# position_sensors.net
KiCad netlist of a schematic drawn in Altium Designer
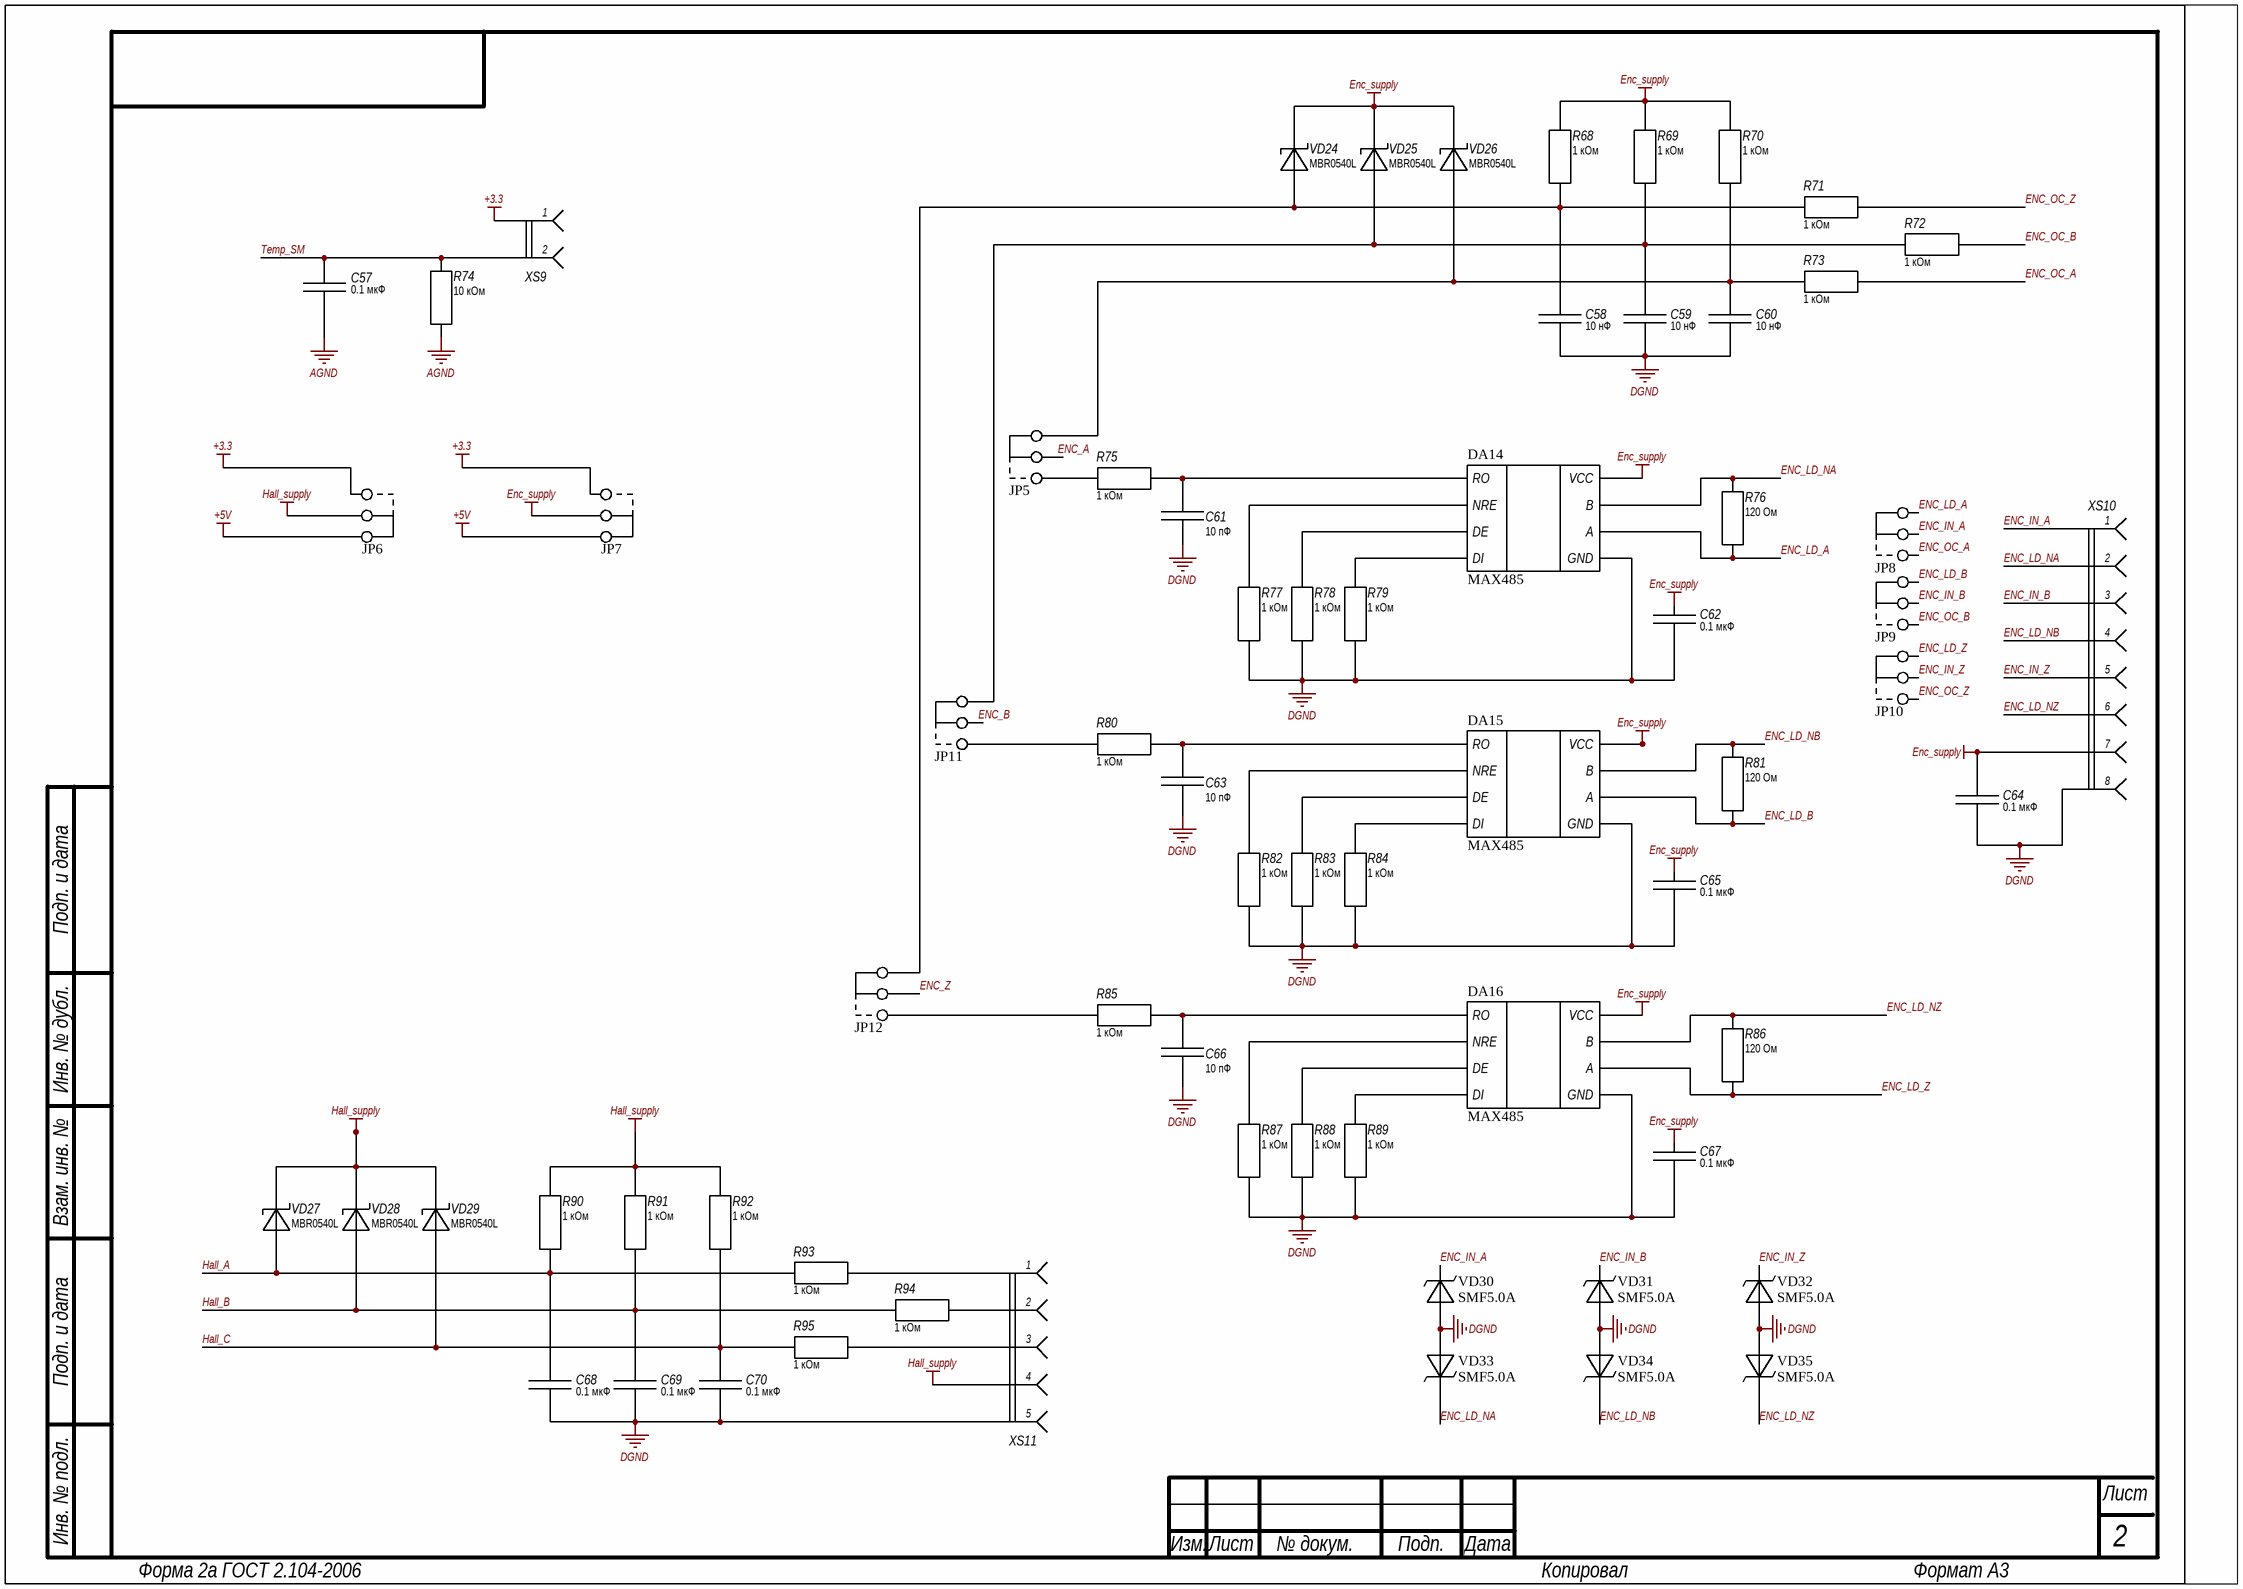
[diagram p0: position_sensors.SchDoc]

(export (version "E")
  (design (tool "Eeschema 10.0.6"))
  (components
    (comp (ref "C57")
      (value "0.1 мкФ")
      (footprint "CC0805")
      (fields (field (name "VOLTAGE") "50 В") (field (name "Comment") "Capacitor"))
      (libsource (lib "Main_components") (part "Capacitor"))
    )
    (comp (ref "C58")
      (value "10 нФ")
      (footprint "CC0805")
      (fields (field (name "VOLTAGE") "16В") (field (name "Comment") "Capacitor"))
      (libsource (lib "Main_components") (part "Capacitor"))
    )
    (comp (ref "C59")
      (value "10 нФ")
      (footprint "CC0805")
      (fields (field (name "VOLTAGE") "16В") (field (name "Comment") "Capacitor"))
      (libsource (lib "Main_components") (part "Capacitor"))
    )
    (comp (ref "C60")
      (value "10 нФ")
      (footprint "CC0603")
      (fields (field (name "VOLTAGE") "50В") (field (name "Comment") "Capacitor"))
      (libsource (lib "Main_components") (part "Capacitor"))
    )
    (comp (ref "C61")
      (value "10 пФ")
      (footprint "CC0603")
      (fields (field (name "VOLTAGE") "50В") (field (name "Comment") "Capacitor"))
      (libsource (lib "Main_components") (part "Capacitor"))
    )
    (comp (ref "C62")
      (value "0.1 мкФ")
      (footprint "CC0603")
      (fields (field (name "VOLTAGE") "16В") (field (name "Comment") "Capacitor"))
      (libsource (lib "Main_components") (part "Capacitor"))
    )
    (comp (ref "C63")
      (value "10 пФ")
      (footprint "CC0603")
      (fields (field (name "VOLTAGE") "50В") (field (name "Comment") "Capacitor"))
      (libsource (lib "Main_components") (part "Capacitor"))
    )
    (comp (ref "C64")
      (value "0.1 мкФ")
      (footprint "CC0603")
      (fields (field (name "VOLTAGE") "16В") (field (name "Comment") "Capacitor"))
      (libsource (lib "Main_components") (part "Capacitor"))
    )
    (comp (ref "C65")
      (value "0.1 мкФ")
      (footprint "CC0603")
      (fields (field (name "VOLTAGE") "16В") (field (name "Comment") "Capacitor"))
      (libsource (lib "Main_components") (part "Capacitor"))
    )
    (comp (ref "C66")
      (value "10 пФ")
      (footprint "CC0603")
      (fields (field (name "VOLTAGE") "50В") (field (name "Comment") "Capacitor"))
      (libsource (lib "Main_components") (part "Capacitor"))
    )
    (comp (ref "C67")
      (value "0.1 мкФ")
      (footprint "CC0603")
      (fields (field (name "VOLTAGE") "16В") (field (name "Comment") "Capacitor"))
      (libsource (lib "Main_components") (part "Capacitor"))
    )
    (comp (ref "C68")
      (value "0.1 мкФ")
      (footprint "CC0805")
      (fields (field (name "VOLTAGE") "50В") (field (name "Comment") "Capacitor"))
      (libsource (lib "Main_components") (part "Capacitor"))
    )
    (comp (ref "C69")
      (value "0.1 мкФ")
      (footprint "CC0805")
      (fields (field (name "VOLTAGE") "50В") (field (name "Comment") "Capacitor"))
      (libsource (lib "Main_components") (part "Capacitor"))
    )
    (comp (ref "C70")
      (value "0.1 мкФ")
      (footprint "CC0805")
      (fields (field (name "VOLTAGE") "50В") (field (name "Comment") "Capacitor"))
      (libsource (lib "Main_components") (part "Capacitor"))
    )
    (comp (ref "DA14")
      (value "MAX485")
      (footprint "SO8")
      (libsource (lib "Microcircuits") (part "MAX485ESA"))
    )
    (comp (ref "DA15")
      (value "MAX485")
      (footprint "SO8")
      (libsource (lib "Microcircuits") (part "MAX485ESA"))
    )
    (comp (ref "DA16")
      (value "MAX485")
      (footprint "SO8")
      (libsource (lib "Microcircuits") (part "MAX485ESA"))
    )
    (comp (ref "JP5") (value "Jumper") (footprint "PLS3") (libsource (lib "Connectors") (part "Jumper")))
    (comp (ref "JP6") (value "Jumper") (footprint "PLS3") (libsource (lib "Connectors") (part "Jumper")))
    (comp (ref "JP7") (value "Jumper") (footprint "PLS3") (libsource (lib "Connectors") (part "Jumper")))
    (comp (ref "JP8") (value "Jumper") (footprint "PLS3") (libsource (lib "Connectors") (part "Jumper")))
    (comp (ref "JP9") (value "Jumper") (footprint "PLS3") (libsource (lib "Connectors") (part "Jumper")))
    (comp (ref "JP10") (value "Jumper") (footprint "PLS3") (libsource (lib "Connectors") (part "Jumper")))
    (comp (ref "JP11") (value "Jumper") (footprint "PLS3") (libsource (lib "Connectors") (part "Jumper")))
    (comp (ref "JP12") (value "Jumper") (footprint "PLS3") (libsource (lib "Connectors") (part "Jumper")))
    (comp (ref "R68")
      (value "1 кОм")
      (footprint "RC1206")
      (fields (field (name "POWER") "250 мВт") (field (name "Comment") "Resistor"))
      (libsource (lib "Main_components") (part "Resistor"))
    )
    (comp (ref "R69")
      (value "1 кОм")
      (footprint "RC1206")
      (fields (field (name "POWER") "250 мВт") (field (name "Comment") "Resistor"))
      (libsource (lib "Main_components") (part "Resistor"))
    )
    (comp (ref "R70")
      (value "1 кОм")
      (footprint "RC1206")
      (fields (field (name "POWER") "250 мВт") (field (name "Comment") "Resistor"))
      (libsource (lib "Main_components") (part "Resistor"))
    )
    (comp (ref "R71")
      (value "1 кОм")
      (footprint "RC1206")
      (fields (field (name "POWER") "250 мВт") (field (name "Comment") "Resistor"))
      (libsource (lib "Main_components") (part "Resistor"))
    )
    (comp (ref "R72")
      (value "1 кОм")
      (footprint "RC1206")
      (fields (field (name "POWER") "250 мВт") (field (name "Comment") "Resistor"))
      (libsource (lib "Main_components") (part "Resistor"))
    )
    (comp (ref "R73")
      (value "1 кОм")
      (footprint "RC1206")
      (fields (field (name "POWER") "250 мВт") (field (name "Comment") "Resistor"))
      (libsource (lib "Main_components") (part "Resistor"))
    )
    (comp (ref "R74")
      (value "10 кОм")
      (footprint "RC0805")
      (fields (field (name "POWER") "125 мВт") (field (name "Comment") "Resistor"))
      (libsource (lib "Main_components") (part "Resistor"))
    )
    (comp (ref "R75")
      (value "1 кОм")
      (footprint "RC0603")
      (fields (field (name "POWER") "100мВт") (field (name "Comment") "Resistor"))
      (libsource (lib "Main_components") (part "Resistor"))
    )
    (comp (ref "R76")
      (value "120 Ом")
      (footprint "RC1206")
      (fields (field (name "POWER") "250 мВт") (field (name "Comment") "Resistor"))
      (libsource (lib "Main_components") (part "Resistor"))
    )
    (comp (ref "R77")
      (value "1 кОм")
      (footprint "RC0603")
      (fields (field (name "POWER") "100 мВт") (field (name "Comment") "Resistor"))
      (libsource (lib "Main_components") (part "Resistor"))
    )
    (comp (ref "R78")
      (value "1 кОм")
      (footprint "RC0603")
      (fields (field (name "POWER") "100 мВт") (field (name "Comment") "Resistor"))
      (libsource (lib "Main_components") (part "Resistor"))
    )
    (comp (ref "R79")
      (value "1 кОм")
      (footprint "RC0603")
      (fields (field (name "POWER") "100 мВт") (field (name "Comment") "Resistor"))
      (libsource (lib "Main_components") (part "Resistor"))
    )
    (comp (ref "R80")
      (value "1 кОм")
      (footprint "RC0603")
      (fields (field (name "POWER") "100мВт") (field (name "Comment") "Resistor"))
      (libsource (lib "Main_components") (part "Resistor"))
    )
    (comp (ref "R81")
      (value "120 Ом")
      (footprint "RC1206")
      (fields (field (name "POWER") "250 мВт") (field (name "Comment") "Resistor"))
      (libsource (lib "Main_components") (part "Resistor"))
    )
    (comp (ref "R82")
      (value "1 кОм")
      (footprint "RC0603")
      (fields (field (name "POWER") "100 мВт") (field (name "Comment") "Resistor"))
      (libsource (lib "Main_components") (part "Resistor"))
    )
    (comp (ref "R83")
      (value "1 кОм")
      (footprint "RC0603")
      (fields (field (name "POWER") "100 мВт") (field (name "Comment") "Resistor"))
      (libsource (lib "Main_components") (part "Resistor"))
    )
    (comp (ref "R84")
      (value "1 кОм")
      (footprint "RC0603")
      (fields (field (name "POWER") "100 мВт") (field (name "Comment") "Resistor"))
      (libsource (lib "Main_components") (part "Resistor"))
    )
    (comp (ref "R85")
      (value "1 кОм")
      (footprint "RC0603")
      (fields (field (name "POWER") "100мВт") (field (name "Comment") "Resistor"))
      (libsource (lib "Main_components") (part "Resistor"))
    )
    (comp (ref "R86")
      (value "120 Ом")
      (footprint "RC1206")
      (fields (field (name "POWER") "250 мВт") (field (name "Comment") "Resistor"))
      (libsource (lib "Main_components") (part "Resistor"))
    )
    (comp (ref "R87")
      (value "1 кОм")
      (footprint "RC0603")
      (fields (field (name "POWER") "100 мВт") (field (name "Comment") "Resistor"))
      (libsource (lib "Main_components") (part "Resistor"))
    )
    (comp (ref "R88")
      (value "1 кОм")
      (footprint "RC0603")
      (fields (field (name "POWER") "100 мВт") (field (name "Comment") "Resistor"))
      (libsource (lib "Main_components") (part "Resistor"))
    )
    (comp (ref "R89")
      (value "1 кОм")
      (footprint "RC0603")
      (fields (field (name "POWER") "100 мВт") (field (name "Comment") "Resistor"))
      (libsource (lib "Main_components") (part "Resistor"))
    )
    (comp (ref "R90")
      (value "1 кОм")
      (footprint "RC1206")
      (fields (field (name "POWER") "250 мВт") (field (name "Comment") "Resistor"))
      (libsource (lib "Main_components") (part "Resistor"))
    )
    (comp (ref "R91")
      (value "1 кОм")
      (footprint "RC1206")
      (fields (field (name "POWER") "250 мВт") (field (name "Comment") "Resistor"))
      (libsource (lib "Main_components") (part "Resistor"))
    )
    (comp (ref "R92")
      (value "1 кОм")
      (footprint "RC1206")
      (fields (field (name "POWER") "250 мВт") (field (name "Comment") "Resistor"))
      (libsource (lib "Main_components") (part "Resistor"))
    )
    (comp (ref "R93")
      (value "1 кОм")
      (footprint "RC1206")
      (fields (field (name "POWER") "250 мВт") (field (name "Comment") "Resistor"))
      (libsource (lib "Main_components") (part "Resistor"))
    )
    (comp (ref "R94")
      (value "1 кОм")
      (footprint "RC1206")
      (fields (field (name "POWER") "250 мВт") (field (name "Comment") "Resistor"))
      (libsource (lib "Main_components") (part "Resistor"))
    )
    (comp (ref "R95")
      (value "1 кОм")
      (footprint "RC1206")
      (fields (field (name "POWER") "250 мВт") (field (name "Comment") "Resistor"))
      (libsource (lib "Main_components") (part "Resistor"))
    )
    (comp (ref "VD24")
      (value "MBR0540L")
      (footprint "SOD123")
      (libsource (lib "Main_components") (part "Shotki"))
    )
    (comp (ref "VD25")
      (value "MBR0540L")
      (footprint "SOD123")
      (libsource (lib "Main_components") (part "Shotki"))
    )
    (comp (ref "VD26")
      (value "MBR0540L")
      (footprint "SOD123")
      (libsource (lib "Main_components") (part "Shotki"))
    )
    (comp (ref "VD27")
      (value "MBR0540L")
      (footprint "SOD123")
      (libsource (lib "Main_components") (part "Shotki"))
    )
    (comp (ref "VD28")
      (value "MBR0540L")
      (footprint "SOD123")
      (libsource (lib "Main_components") (part "Shotki"))
    )
    (comp (ref "VD29")
      (value "MBR0540L")
      (footprint "SOD123")
      (libsource (lib "Main_components") (part "Shotki"))
    )
    (comp (ref "VD30")
      (value "SMF5.0A")
      (footprint "D0-124AC")
      (libsource (lib "Main_components") (part "TVS Diode"))
    )
    (comp (ref "VD31")
      (value "SMF5.0A")
      (footprint "D0-124AC")
      (libsource (lib "Main_components") (part "TVS Diode"))
    )
    (comp (ref "VD32")
      (value "SMF5.0A")
      (footprint "D0-124AC")
      (libsource (lib "Main_components") (part "TVS Diode"))
    )
    (comp (ref "VD33")
      (value "SMF5.0A")
      (footprint "D0-124AC")
      (libsource (lib "Main_components") (part "TVS Diode"))
    )
    (comp (ref "VD34")
      (value "SMF5.0A")
      (footprint "D0-124AC")
      (libsource (lib "Main_components") (part "TVS Diode"))
    )
    (comp (ref "VD35")
      (value "SMF5.0A")
      (footprint "D0-124AC")
      (libsource (lib "Main_components") (part "TVS Diode"))
    )
    (comp (ref "XS9")
      (value "JST-Male-2")
      (footprint "JST-2")
      (libsource (lib "Connectors") (part "JST-Male-2"))
    )
    (comp (ref "XS10")
      (value "DG141V-2.54-05P-14-00AH")
      (footprint "DG141V-2.54-08P")
      (libsource (lib "Connectors") (part "DG141V-2.54-08P-14-00A(H)"))
    )
    (comp (ref "XS11")
      (value "DG141V-2.54-05P-14-00AH")
      (footprint "DG141V-2.54-05P")
      (libsource (lib "Connectors") (part "DG141V-2.54-05P-14-00AH"))
    )
  )
  (nets
    (net (code "1") (name "+3.3") (class "Default")
      (node (ref "JP6") (pin "1") (pinfunction "4_1") (pintype "passive"))
      (node (ref "JP7") (pin "1") (pinfunction "4_1") (pintype "passive"))
      (node (ref "XS9") (pin "1") (pinfunction "1_1") (pintype "passive"))
    )
    (net (code "2") (name "+5V") (class "Default")
      (node (ref "JP6") (pin "3") (pinfunction "6_3") (pintype "passive"))
      (node (ref "JP7") (pin "3") (pinfunction "6_3") (pintype "passive"))
    )
    (net (code "3") (name "/ENC_A") (class "Default")
      (node (ref "JP5") (pin "2") (pinfunction "5_2") (pintype "passive"))
    )
    (net (code "4") (name "/ENC_B") (class "Default")
      (node (ref "JP11") (pin "2") (pinfunction "5_2") (pintype "passive"))
    )
    (net (code "5") (name "/ENC_IN_A") (class "Default")
      (node (ref "JP8") (pin "2") (pinfunction "5_2") (pintype "passive"))
      (node (ref "VD30") (pin "C") (pinfunction "C_C") (pintype "passive"))
      (node (ref "XS10") (pin "1") (pinfunction "1_1") (pintype "passive"))
    )
    (net (code "6") (name "/ENC_IN_B") (class "Default")
      (node (ref "JP9") (pin "2") (pinfunction "5_2") (pintype "passive"))
      (node (ref "VD31") (pin "C") (pinfunction "C_C") (pintype "passive"))
      (node (ref "XS10") (pin "3") (pinfunction "3_3") (pintype "passive"))
    )
    (net (code "7") (name "/ENC_IN_Z") (class "Default")
      (node (ref "JP10") (pin "2") (pinfunction "5_2") (pintype "passive"))
      (node (ref "VD32") (pin "C") (pinfunction "C_C") (pintype "passive"))
      (node (ref "XS10") (pin "5") (pinfunction "5_5") (pintype "passive"))
    )
    (net (code "8") (name "/ENC_LD_A") (class "Default")
      (node (ref "DA14") (pin "7") (pinfunction "A_7") (pintype "passive"))
      (node (ref "JP8") (pin "3") (pinfunction "6_3") (pintype "passive"))
      (node (ref "R76") (pin "1") (pinfunction "1_1") (pintype "passive"))
    )
    (net (code "9") (name "/ENC_LD_B") (class "Default")
      (node (ref "DA15") (pin "7") (pinfunction "A_7") (pintype "passive"))
      (node (ref "JP9") (pin "3") (pinfunction "6_3") (pintype "passive"))
      (node (ref "R81") (pin "1") (pinfunction "1_1") (pintype "passive"))
    )
    (net (code "10") (name "/ENC_LD_NA") (class "Default")
      (node (ref "DA14") (pin "6") (pinfunction "B_6") (pintype "passive"))
      (node (ref "R76") (pin "2") (pinfunction "2_2") (pintype "passive"))
      (node (ref "VD33") (pin "C") (pinfunction "C_C") (pintype "passive"))
      (node (ref "XS10") (pin "2") (pinfunction "2_2") (pintype "passive"))
    )
    (net (code "11") (name "/ENC_LD_NB") (class "Default")
      (node (ref "DA15") (pin "6") (pinfunction "B_6") (pintype "passive"))
      (node (ref "R81") (pin "2") (pinfunction "2_2") (pintype "passive"))
      (node (ref "VD34") (pin "C") (pinfunction "C_C") (pintype "passive"))
      (node (ref "XS10") (pin "4") (pinfunction "4_4") (pintype "passive"))
    )
    (net (code "12") (name "/ENC_LD_NZ") (class "Default")
      (node (ref "DA16") (pin "6") (pinfunction "B_6") (pintype "passive"))
      (node (ref "R86") (pin "2") (pinfunction "2_2") (pintype "passive"))
      (node (ref "VD35") (pin "C") (pinfunction "C_C") (pintype "passive"))
      (node (ref "XS10") (pin "6") (pinfunction "6_6") (pintype "passive"))
    )
    (net (code "13") (name "/ENC_LD_Z") (class "Default")
      (node (ref "DA16") (pin "7") (pinfunction "A_7") (pintype "passive"))
      (node (ref "JP10") (pin "3") (pinfunction "6_3") (pintype "passive"))
      (node (ref "R86") (pin "1") (pinfunction "1_1") (pintype "passive"))
    )
    (net (code "14") (name "/ENC_OC_A") (class "Default")
      (node (ref "JP8") (pin "1") (pinfunction "4_1") (pintype "passive"))
      (node (ref "R73") (pin "2") (pinfunction "2_2") (pintype "passive"))
    )
    (net (code "15") (name "/ENC_OC_B") (class "Default")
      (node (ref "JP9") (pin "1") (pinfunction "4_1") (pintype "passive"))
      (node (ref "R72") (pin "2") (pinfunction "2_2") (pintype "passive"))
    )
    (net (code "16") (name "/ENC_OC_Z") (class "Default")
      (node (ref "JP10") (pin "1") (pinfunction "4_1") (pintype "passive"))
      (node (ref "R71") (pin "2") (pinfunction "2_2") (pintype "passive"))
    )
    (net (code "17") (name "/ENC_Z") (class "Default")
      (node (ref "JP12") (pin "2") (pinfunction "5_2") (pintype "passive"))
    )
    (net (code "18") (name "/Hall_A") (class "Default")
      (node (ref "C68") (pin "2") (pinfunction "2_2") (pintype "passive"))
      (node (ref "R90") (pin "1") (pinfunction "1_1") (pintype "passive"))
      (node (ref "R93") (pin "1") (pinfunction "1_1") (pintype "passive"))
      (node (ref "VD27") (pin "A") (pinfunction "A_A") (pintype "passive"))
    )
    (net (code "19") (name "/Hall_B") (class "Default")
      (node (ref "C69") (pin "2") (pinfunction "2_2") (pintype "passive"))
      (node (ref "R91") (pin "1") (pinfunction "1_1") (pintype "passive"))
      (node (ref "R94") (pin "1") (pinfunction "1_1") (pintype "passive"))
      (node (ref "VD28") (pin "A") (pinfunction "A_A") (pintype "passive"))
    )
    (net (code "20") (name "/Hall_C") (class "Default")
      (node (ref "C70") (pin "2") (pinfunction "2_2") (pintype "passive"))
      (node (ref "R92") (pin "1") (pinfunction "1_1") (pintype "passive"))
      (node (ref "R95") (pin "1") (pinfunction "1_1") (pintype "passive"))
      (node (ref "VD29") (pin "A") (pinfunction "A_A") (pintype "passive"))
    )
    (net (code "21") (name "/Temp_SM") (class "Default")
      (node (ref "C57") (pin "2") (pinfunction "2_2") (pintype "passive"))
      (node (ref "R74") (pin "1") (pinfunction "1_1") (pintype "passive"))
      (node (ref "XS9") (pin "2") (pinfunction "2_2") (pintype "passive"))
    )
    (net (code "22") (name "AGND") (class "Default")
      (node (ref "C57") (pin "1") (pinfunction "1_1") (pintype "passive"))
      (node (ref "R74") (pin "2") (pinfunction "2_2") (pintype "passive"))
    )
    (net (code "23") (name "DGND") (class "Default")
      (node (ref "C58") (pin "1") (pinfunction "1_1") (pintype "passive"))
      (node (ref "C59") (pin "1") (pinfunction "1_1") (pintype "passive"))
      (node (ref "C60") (pin "1") (pinfunction "1_1") (pintype "passive"))
      (node (ref "C61") (pin "2") (pinfunction "2_2") (pintype "passive"))
      (node (ref "C62") (pin "1") (pinfunction "1_1") (pintype "passive"))
      (node (ref "C63") (pin "2") (pinfunction "2_2") (pintype "passive"))
      (node (ref "C64") (pin "1") (pinfunction "1_1") (pintype "passive"))
      (node (ref "C65") (pin "1") (pinfunction "1_1") (pintype "passive"))
      (node (ref "C66") (pin "2") (pinfunction "2_2") (pintype "passive"))
      (node (ref "C67") (pin "1") (pinfunction "1_1") (pintype "passive"))
      (node (ref "C68") (pin "1") (pinfunction "1_1") (pintype "passive"))
      (node (ref "C69") (pin "1") (pinfunction "1_1") (pintype "passive"))
      (node (ref "C70") (pin "1") (pinfunction "1_1") (pintype "passive"))
      (node (ref "DA14") (pin "8") (pinfunction "GND_8") (pintype "passive"))
      (node (ref "DA15") (pin "8") (pinfunction "GND_8") (pintype "passive"))
      (node (ref "DA16") (pin "8") (pinfunction "GND_8") (pintype "passive"))
      (node (ref "R77") (pin "2") (pinfunction "2_2") (pintype "passive"))
      (node (ref "R78") (pin "2") (pinfunction "2_2") (pintype "passive"))
      (node (ref "R79") (pin "2") (pinfunction "2_2") (pintype "passive"))
      (node (ref "R82") (pin "2") (pinfunction "2_2") (pintype "passive"))
      (node (ref "R83") (pin "2") (pinfunction "2_2") (pintype "passive"))
      (node (ref "R84") (pin "2") (pinfunction "2_2") (pintype "passive"))
      (node (ref "R87") (pin "2") (pinfunction "2_2") (pintype "passive"))
      (node (ref "R88") (pin "2") (pinfunction "2_2") (pintype "passive"))
      (node (ref "R89") (pin "2") (pinfunction "2_2") (pintype "passive"))
      (node (ref "VD30") (pin "A") (pinfunction "A_A") (pintype "passive"))
      (node (ref "VD31") (pin "A") (pinfunction "A_A") (pintype "passive"))
      (node (ref "VD32") (pin "A") (pinfunction "A_A") (pintype "passive"))
      (node (ref "VD33") (pin "A") (pinfunction "A_A") (pintype "passive"))
      (node (ref "VD34") (pin "A") (pinfunction "A_A") (pintype "passive"))
      (node (ref "VD35") (pin "A") (pinfunction "A_A") (pintype "passive"))
      (node (ref "XS10") (pin "8") (pinfunction "8_8") (pintype "passive"))
      (node (ref "XS11") (pin "5") (pinfunction "5_5") (pintype "passive"))
    )
    (net (code "24") (name "Enc_supply") (class "Default")
      (node (ref "C62") (pin "2") (pinfunction "2_2") (pintype "passive"))
      (node (ref "C64") (pin "2") (pinfunction "2_2") (pintype "passive"))
      (node (ref "C65") (pin "2") (pinfunction "2_2") (pintype "passive"))
      (node (ref "C67") (pin "2") (pinfunction "2_2") (pintype "passive"))
      (node (ref "DA14") (pin "5") (pinfunction "VCC_5") (pintype "passive"))
      (node (ref "DA15") (pin "5") (pinfunction "VCC_5") (pintype "passive"))
      (node (ref "DA16") (pin "5") (pinfunction "VCC_5") (pintype "passive"))
      (node (ref "JP7") (pin "2") (pinfunction "5_2") (pintype "passive"))
      (node (ref "R68") (pin "2") (pinfunction "2_2") (pintype "passive"))
      (node (ref "R69") (pin "2") (pinfunction "2_2") (pintype "passive"))
      (node (ref "R70") (pin "2") (pinfunction "2_2") (pintype "passive"))
      (node (ref "VD24") (pin "C") (pinfunction "C_C") (pintype "passive"))
      (node (ref "VD25") (pin "C") (pinfunction "C_C") (pintype "passive"))
      (node (ref "VD26") (pin "C") (pinfunction "C_C") (pintype "passive"))
      (node (ref "XS10") (pin "7") (pinfunction "7_7") (pintype "passive"))
    )
    (net (code "25") (name "Hall_supply") (class "Default")
      (node (ref "JP6") (pin "2") (pinfunction "5_2") (pintype "passive"))
      (node (ref "R90") (pin "2") (pinfunction "2_2") (pintype "passive"))
      (node (ref "R91") (pin "2") (pinfunction "2_2") (pintype "passive"))
      (node (ref "R92") (pin "2") (pinfunction "2_2") (pintype "passive"))
      (node (ref "VD27") (pin "C") (pinfunction "C_C") (pintype "passive"))
      (node (ref "VD28") (pin "C") (pinfunction "C_C") (pintype "passive"))
      (node (ref "VD29") (pin "C") (pinfunction "C_C") (pintype "passive"))
      (node (ref "XS11") (pin "4") (pinfunction "4_4") (pintype "passive"))
    )
    (net (code "26") (name "Net-(DA14-DE)") (class "Default")
      (node (ref "DA14") (pin "3") (pinfunction "DE_3") (pintype "passive"))
      (node (ref "R78") (pin "1") (pinfunction "1_1") (pintype "passive"))
    )
    (net (code "27") (name "Net-(DA14-DI)") (class "Default")
      (node (ref "DA14") (pin "4") (pinfunction "DI_4") (pintype "passive"))
      (node (ref "R79") (pin "1") (pinfunction "1_1") (pintype "passive"))
    )
    (net (code "28") (name "Net-(DA14-NRE)") (class "Default")
      (node (ref "DA14") (pin "2") (pinfunction "NRE_2") (pintype "passive"))
      (node (ref "R77") (pin "1") (pinfunction "1_1") (pintype "passive"))
    )
    (net (code "29") (name "Net-(DA14-RO)") (class "Default")
      (node (ref "C61") (pin "1") (pinfunction "1_1") (pintype "passive"))
      (node (ref "DA14") (pin "1") (pinfunction "RO_1") (pintype "passive"))
      (node (ref "R75") (pin "1") (pinfunction "1_1") (pintype "passive"))
    )
    (net (code "30") (name "Net-(DA15-DE)") (class "Default")
      (node (ref "DA15") (pin "3") (pinfunction "DE_3") (pintype "passive"))
      (node (ref "R83") (pin "1") (pinfunction "1_1") (pintype "passive"))
    )
    (net (code "31") (name "Net-(DA15-DI)") (class "Default")
      (node (ref "DA15") (pin "4") (pinfunction "DI_4") (pintype "passive"))
      (node (ref "R84") (pin "1") (pinfunction "1_1") (pintype "passive"))
    )
    (net (code "32") (name "Net-(DA15-NRE)") (class "Default")
      (node (ref "DA15") (pin "2") (pinfunction "NRE_2") (pintype "passive"))
      (node (ref "R82") (pin "1") (pinfunction "1_1") (pintype "passive"))
    )
    (net (code "33") (name "Net-(DA15-RO)") (class "Default")
      (node (ref "C63") (pin "1") (pinfunction "1_1") (pintype "passive"))
      (node (ref "DA15") (pin "1") (pinfunction "RO_1") (pintype "passive"))
      (node (ref "R80") (pin "1") (pinfunction "1_1") (pintype "passive"))
    )
    (net (code "34") (name "Net-(DA16-DE)") (class "Default")
      (node (ref "DA16") (pin "3") (pinfunction "DE_3") (pintype "passive"))
      (node (ref "R88") (pin "1") (pinfunction "1_1") (pintype "passive"))
    )
    (net (code "35") (name "Net-(DA16-DI)") (class "Default")
      (node (ref "DA16") (pin "4") (pinfunction "DI_4") (pintype "passive"))
      (node (ref "R89") (pin "1") (pinfunction "1_1") (pintype "passive"))
    )
    (net (code "36") (name "Net-(DA16-NRE)") (class "Default")
      (node (ref "DA16") (pin "2") (pinfunction "NRE_2") (pintype "passive"))
      (node (ref "R87") (pin "1") (pinfunction "1_1") (pintype "passive"))
    )
    (net (code "37") (name "Net-(DA16-RO)") (class "Default")
      (node (ref "C66") (pin "1") (pinfunction "1_1") (pintype "passive"))
      (node (ref "DA16") (pin "1") (pinfunction "RO_1") (pintype "passive"))
      (node (ref "R85") (pin "1") (pinfunction "1_1") (pintype "passive"))
    )
    (net (code "38") (name "Net-(JP5-4)") (class "Default")
      (node (ref "JP5") (pin "1") (pinfunction "4_1") (pintype "passive"))
      (node (ref "R75") (pin "2") (pinfunction "2_2") (pintype "passive"))
    )
    (net (code "39") (name "Net-(JP5-6)") (class "Default")
      (node (ref "C60") (pin "2") (pinfunction "2_2") (pintype "passive"))
      (node (ref "JP5") (pin "3") (pinfunction "6_3") (pintype "passive"))
      (node (ref "R70") (pin "1") (pinfunction "1_1") (pintype "passive"))
      (node (ref "R73") (pin "1") (pinfunction "1_1") (pintype "passive"))
      (node (ref "VD26") (pin "A") (pinfunction "A_A") (pintype "passive"))
    )
    (net (code "40") (name "Net-(JP11-4)") (class "Default")
      (node (ref "JP11") (pin "1") (pinfunction "4_1") (pintype "passive"))
      (node (ref "R80") (pin "2") (pinfunction "2_2") (pintype "passive"))
    )
    (net (code "41") (name "Net-(JP11-6)") (class "Default")
      (node (ref "C59") (pin "2") (pinfunction "2_2") (pintype "passive"))
      (node (ref "JP11") (pin "3") (pinfunction "6_3") (pintype "passive"))
      (node (ref "R69") (pin "1") (pinfunction "1_1") (pintype "passive"))
      (node (ref "R72") (pin "1") (pinfunction "1_1") (pintype "passive"))
      (node (ref "VD25") (pin "A") (pinfunction "A_A") (pintype "passive"))
    )
    (net (code "42") (name "Net-(JP12-4)") (class "Default")
      (node (ref "JP12") (pin "1") (pinfunction "4_1") (pintype "passive"))
      (node (ref "R85") (pin "2") (pinfunction "2_2") (pintype "passive"))
    )
    (net (code "43") (name "Net-(JP12-6)") (class "Default")
      (node (ref "C58") (pin "2") (pinfunction "2_2") (pintype "passive"))
      (node (ref "JP12") (pin "3") (pinfunction "6_3") (pintype "passive"))
      (node (ref "R68") (pin "1") (pinfunction "1_1") (pintype "passive"))
      (node (ref "R71") (pin "1") (pinfunction "1_1") (pintype "passive"))
      (node (ref "VD24") (pin "A") (pinfunction "A_A") (pintype "passive"))
    )
    (net (code "44") (name "Net-(R93-Pad2)") (class "Default")
      (node (ref "R93") (pin "2") (pinfunction "2_2") (pintype "passive"))
      (node (ref "XS11") (pin "1") (pinfunction "1_1") (pintype "passive"))
    )
    (net (code "45") (name "Net-(R94-Pad2)") (class "Default")
      (node (ref "R94") (pin "2") (pinfunction "2_2") (pintype "passive"))
      (node (ref "XS11") (pin "2") (pinfunction "2_2") (pintype "passive"))
    )
    (net (code "46") (name "Net-(R95-Pad2)") (class "Default")
      (node (ref "R95") (pin "2") (pinfunction "2_2") (pintype "passive"))
      (node (ref "XS11") (pin "3") (pinfunction "3_3") (pintype "passive"))
    )
  )
)
